# FPGA_165B_Repeat_DigitalIO.net
KiCad netlist of a schematic drawn in Altium Designer
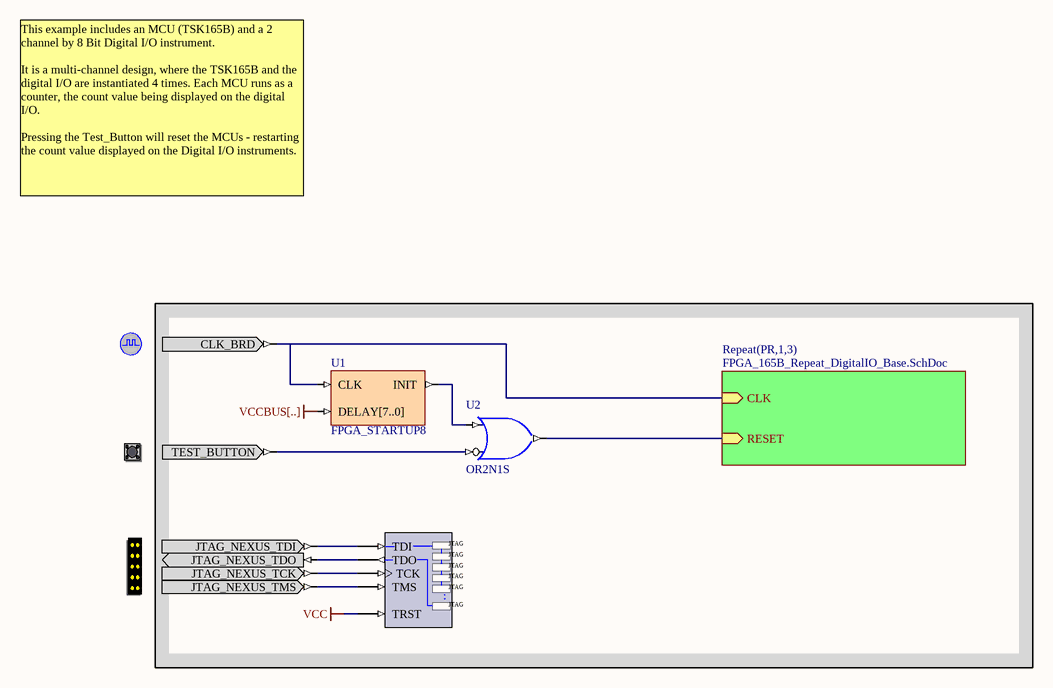
[diagram p0: FPGA_165B_Repeat_DigitalIO.SchDoc]

(export (version "E")
  (design (tool "Eeschema 10.0.6"))
  (components
    (comp (ref "CLOCK_BOARD")
      (value "CLOCK_BOARD")
      (description "Global System Clock Supply")
      (fields (field (name "PUBLISHER") "Altium Limited"))
      (libsource (lib "FPGA EvalBoard Port-Plugin") (part "CLOCK_BOARD"))
    )
    (comp (ref "NEXUS_JTAG_CONNECTOR")
      (value "NEXUS_JTAG_CONNECTOR")
      (description "JTAG Port")
      (fields (field (name "PUBLISHER") "Altium Limited"))
      (libsource (lib "FPGA EvalBoard Port-Plugin") (part "NEXUS_JTAG_CONNECTOR"))
    )
    (comp (ref "NEXUS_JTAG_PORT")
      (value "NEXUS_JTAG_PORT")
      (description "Soft Nexus-Chain Connector")
      (fields (field (name "PUBLISHER") "Altium Limited"))
      (libsource (lib "FPGA Generic") (part "NEXUS_JTAG_PORT"))
    )
    (comp (ref "TEST_BUTTON")
      (value "TEST_BUTTON")
      (description "Test Button")
      (fields (field (name "PUBLISHER") "Altium Limited"))
      (libsource (lib "FPGA EvalBoard Port-Plugin") (part "TEST_BUTTON"))
    )
    (comp (ref "U1")
      (value "FPGA_STARTUP8")
      (description "FPGA Startup With 8 Bit Delay")
      (fields (field (name "PUBLISHER") "Altium Hobart Technology Centre"))
      (libsource (lib "FPGA Peripherals") (part "FPGA_STARTUP8"))
    )
    (comp (ref "U2")
      (value "OR2N1S")
      (description "2-Input OR Gate with Active Low A Input, Single Pin Version")
      (fields (field (name "PUBLISHER") "Altium Limited"))
      (libsource (lib "FPGA Generic") (part "OR2N1S"))
    )
  )
  (nets
    (net (code "1") (name "/CLK") (class "Default")
      (node (ref "CLOCK_BOARD") (pin "CLK_BRD") (pinfunction "CLK_BRD_CLK_BRD") (pintype "output"))
      (node (ref "U1") (pin "CLK") (pinfunction "CLK_CLK") (pintype "input"))
    )
    (net (code "2") (name "/RESET") (class "Default")
      (node (ref "U2") (pin "O") (pinfunction "O_O") (pintype "output"))
    )
    (net (code "3") (name "Net-(NEXUS_JTAG_CONNECTOR-PadJTAG_NEXUS_TCK)") (class "Default")
      (node (ref "NEXUS_JTAG_CONNECTOR") (pin "JTAG_NEXUS_TCK") (pinfunction "JTAG_NEXUS_TCK_JTAG_NEXUS_TCK") (pintype "output"))
      (node (ref "NEXUS_JTAG_PORT") (pin "TCK") (pinfunction "TCK_TCK") (pintype "input"))
    )
    (net (code "4") (name "Net-(NEXUS_JTAG_CONNECTOR-PadJTAG_NEXUS_TDI)") (class "Default")
      (node (ref "NEXUS_JTAG_CONNECTOR") (pin "JTAG_NEXUS_TDI") (pinfunction "JTAG_NEXUS_TDI_JTAG_NEXUS_TDI") (pintype "output"))
      (node (ref "NEXUS_JTAG_PORT") (pin "TDI") (pinfunction "TDI_TDI") (pintype "input"))
    )
    (net (code "5") (name "Net-(NEXUS_JTAG_CONNECTOR-PadJTAG_NEXUS_TDO)") (class "Default")
      (node (ref "NEXUS_JTAG_CONNECTOR") (pin "JTAG_NEXUS_TDO") (pinfunction "JTAG_NEXUS_TDO_JTAG_NEXUS_TDO") (pintype "input"))
      (node (ref "NEXUS_JTAG_PORT") (pin "TDO") (pinfunction "TDO_TDO") (pintype "output"))
    )
    (net (code "6") (name "Net-(NEXUS_JTAG_CONNECTOR-PadJTAG_NEXUS_TMS)") (class "Default")
      (node (ref "NEXUS_JTAG_CONNECTOR") (pin "JTAG_NEXUS_TMS") (pinfunction "JTAG_NEXUS_TMS_JTAG_NEXUS_TMS") (pintype "output"))
      (node (ref "NEXUS_JTAG_PORT") (pin "TMS") (pinfunction "TMS_TMS") (pintype "input"))
    )
    (net (code "7") (name "Net-(TEST_BUTTON-PadTEST_BUTTON)") (class "Default")
      (node (ref "TEST_BUTTON") (pin "TEST_BUTTON") (pinfunction "TEST_BUTTON_TEST_BUTTON") (pintype "output"))
      (node (ref "U2") (pin "I0") (pinfunction "I0_I0") (pintype "input"))
    )
    (net (code "8") (name "Net-(U1-PadINIT)") (class "Default")
      (node (ref "U1") (pin "INIT") (pinfunction "INIT_INIT") (pintype "output"))
      (node (ref "U2") (pin "I1") (pinfunction "I1_I1") (pintype "input"))
    )
    (net (code "9") (name "VCC") (class "Default")
      (node (ref "NEXUS_JTAG_PORT") (pin "TRST") (pinfunction "TRST_TRST") (pintype "input"))
    )
    (net (code "10") (name "VCCBUS[..]") (class "Default")
      (node (ref "U1") (pin "DELAY[7..0]") (pinfunction "DELAY[7..0]_DELAY[7..0]") (pintype "input"))
    )
  )
)
